# EmgAcq.net
KiCad netlist of a schematic drawn in Altium Designer
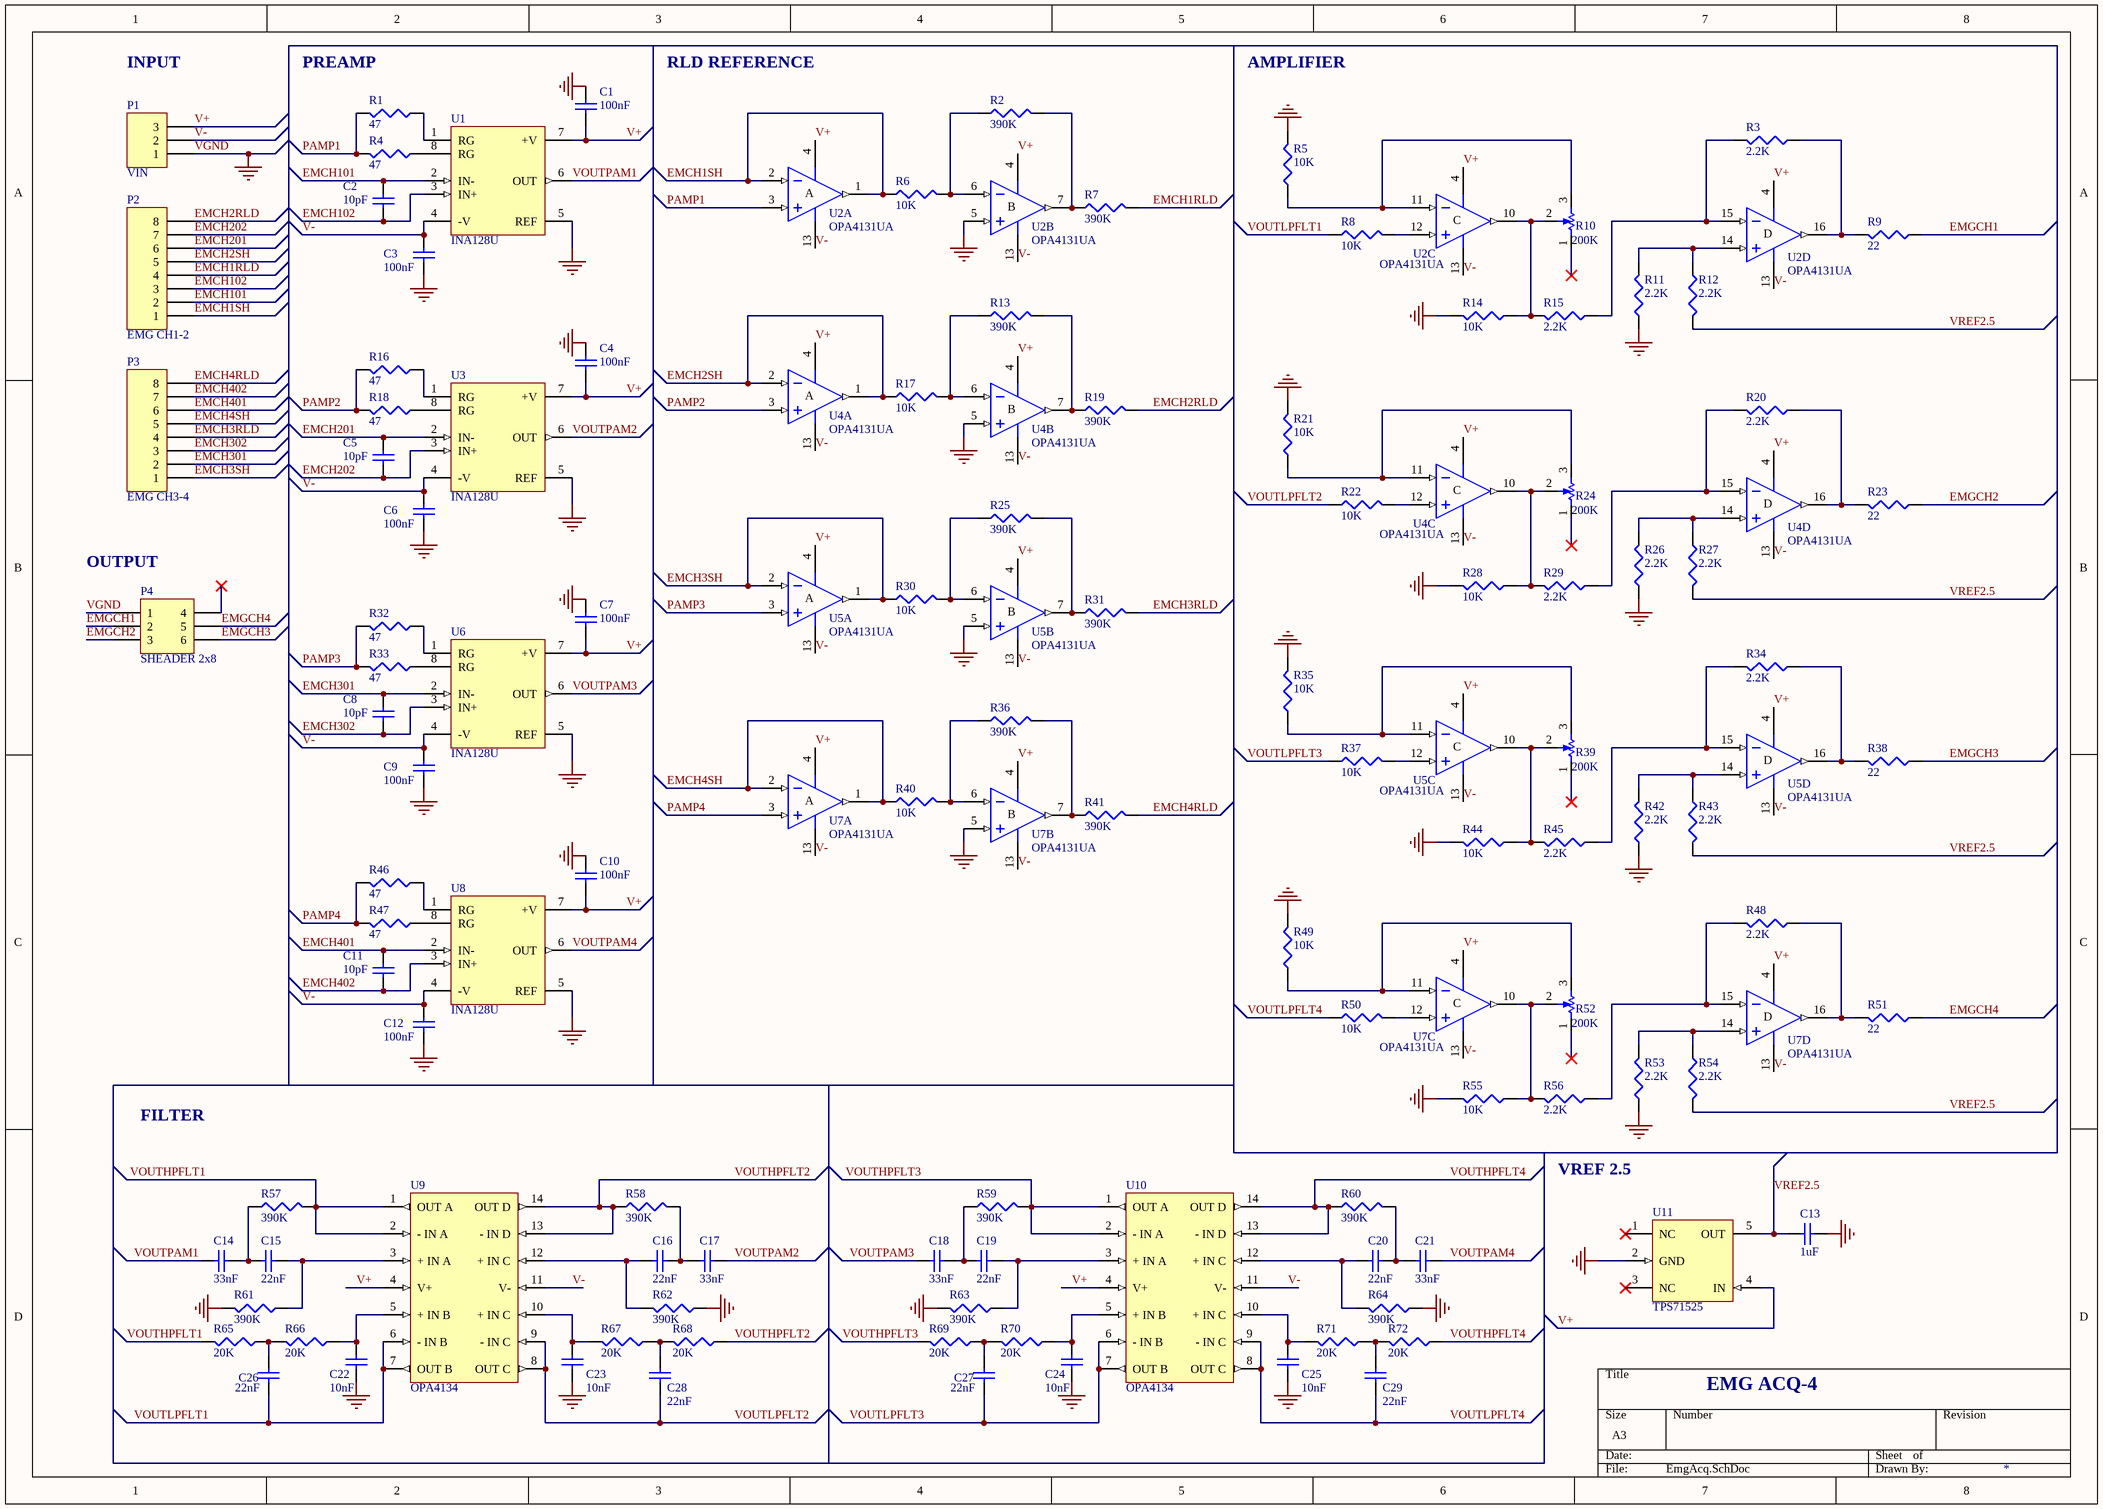
[diagram p0: EmgAcq.SchDoc]

(export (version "E")
  (design (tool "Eeschema 10.0.6"))
  (components
    (comp (ref "C1")
      (value "100nF")
      (footprint "C1206")
      (description "Capacitor (Semiconductor SIM Model)")
      (fields (field (name "Comment") "Cap Semi"))
      (libsource (lib "Miscellaneous Devices") (part "Cap Semi"))
    )
    (comp (ref "C2")
      (value "10pF")
      (footprint "C1206")
      (description "Capacitor (Semiconductor SIM Model)")
      (fields (field (name "Comment") "Cap Semi"))
      (libsource (lib "Miscellaneous Devices") (part "Cap Semi"))
    )
    (comp (ref "C3")
      (value "100nF")
      (footprint "C1206")
      (description "Capacitor (Semiconductor SIM Model)")
      (fields (field (name "Comment") "Cap Semi"))
      (libsource (lib "Miscellaneous Devices") (part "Cap Semi"))
    )
    (comp (ref "C4")
      (value "100nF")
      (footprint "C1206")
      (description "Capacitor (Semiconductor SIM Model)")
      (fields (field (name "Comment") "Cap Semi"))
      (libsource (lib "Miscellaneous Devices") (part "Cap Semi"))
    )
    (comp (ref "C5")
      (value "10pF")
      (footprint "C1206")
      (description "Capacitor (Semiconductor SIM Model)")
      (fields (field (name "Comment") "Cap Semi"))
      (libsource (lib "Miscellaneous Devices") (part "Cap Semi"))
    )
    (comp (ref "C6")
      (value "100nF")
      (footprint "C1206")
      (description "Capacitor (Semiconductor SIM Model)")
      (fields (field (name "Comment") "Cap Semi"))
      (libsource (lib "Miscellaneous Devices") (part "Cap Semi"))
    )
    (comp (ref "C7")
      (value "100nF")
      (footprint "C1206")
      (description "Capacitor (Semiconductor SIM Model)")
      (fields (field (name "Comment") "Cap Semi"))
      (libsource (lib "Miscellaneous Devices") (part "Cap Semi"))
    )
    (comp (ref "C8")
      (value "10pF")
      (footprint "C1206")
      (description "Capacitor (Semiconductor SIM Model)")
      (fields (field (name "Comment") "Cap Semi"))
      (libsource (lib "Miscellaneous Devices") (part "Cap Semi"))
    )
    (comp (ref "C9")
      (value "100nF")
      (footprint "C1206")
      (description "Capacitor (Semiconductor SIM Model)")
      (fields (field (name "Comment") "Cap Semi"))
      (libsource (lib "Miscellaneous Devices") (part "Cap Semi"))
    )
    (comp (ref "C10")
      (value "100nF")
      (footprint "C1206")
      (description "Capacitor (Semiconductor SIM Model)")
      (fields (field (name "Comment") "Cap Semi"))
      (libsource (lib "Miscellaneous Devices") (part "Cap Semi"))
    )
    (comp (ref "C11")
      (value "10pF")
      (footprint "C1206")
      (description "Capacitor (Semiconductor SIM Model)")
      (fields (field (name "Comment") "Cap Semi"))
      (libsource (lib "Miscellaneous Devices") (part "Cap Semi"))
    )
    (comp (ref "C12")
      (value "100nF")
      (footprint "C1206")
      (description "Capacitor (Semiconductor SIM Model)")
      (fields (field (name "Comment") "Cap Semi"))
      (libsource (lib "Miscellaneous Devices") (part "Cap Semi"))
    )
    (comp (ref "C13")
      (value "1uF")
      (footprint "CAPC2012M")
      (description "Capacitor (Semiconductor SIM Model)")
      (fields (field (name "Comment") "Cap Semi"))
      (libsource (lib "Miscellaneous Devices") (part "Cap Semi"))
    )
    (comp (ref "C14")
      (value "33nF")
      (footprint "C1206")
      (description "Capacitor (Semiconductor SIM Model)")
      (fields (field (name "Comment") "Cap Semi"))
      (libsource (lib "Miscellaneous Devices") (part "Cap Semi"))
    )
    (comp (ref "C15")
      (value "22nF")
      (footprint "1608[0603]")
      (description "Capacitor (Semiconductor SIM Model)")
      (fields (field (name "Comment") "Cap Semi"))
      (libsource (lib "Miscellaneous Devices") (part "Cap Semi"))
    )
    (comp (ref "C16")
      (value "22nF")
      (footprint "1608[0603]")
      (description "Capacitor (Semiconductor SIM Model)")
      (fields (field (name "Comment") "Cap Semi"))
      (libsource (lib "Miscellaneous Devices") (part "Cap Semi"))
    )
    (comp (ref "C17")
      (value "33nF")
      (footprint "C1206")
      (description "Capacitor (Semiconductor SIM Model)")
      (fields (field (name "Comment") "Cap Semi"))
      (libsource (lib "Miscellaneous Devices") (part "Cap Semi"))
    )
    (comp (ref "C18")
      (value "33nF")
      (footprint "C1206")
      (description "Capacitor (Semiconductor SIM Model)")
      (fields (field (name "Comment") "Cap Semi"))
      (libsource (lib "Miscellaneous Devices") (part "Cap Semi"))
    )
    (comp (ref "C19")
      (value "22nF")
      (footprint "1608[0603]")
      (description "Capacitor (Semiconductor SIM Model)")
      (fields (field (name "Comment") "Cap Semi"))
      (libsource (lib "Miscellaneous Devices") (part "Cap Semi"))
    )
    (comp (ref "C20")
      (value "22nF")
      (footprint "1608[0603]")
      (description "Capacitor (Semiconductor SIM Model)")
      (fields (field (name "Comment") "Cap Semi"))
      (libsource (lib "Miscellaneous Devices") (part "Cap Semi"))
    )
    (comp (ref "C21")
      (value "33nF")
      (footprint "C1206")
      (description "Capacitor (Semiconductor SIM Model)")
      (fields (field (name "Comment") "Cap Semi"))
      (libsource (lib "Miscellaneous Devices") (part "Cap Semi"))
    )
    (comp (ref "C22")
      (value "10nF")
      (footprint "C1206")
      (description "Capacitor (Semiconductor SIM Model)")
      (fields (field (name "Comment") "Cap Semi"))
      (libsource (lib "Miscellaneous Devices") (part "Cap Semi"))
    )
    (comp (ref "C23")
      (value "10nF")
      (footprint "C1206")
      (description "Capacitor (Semiconductor SIM Model)")
      (fields (field (name "Comment") "Cap Semi"))
      (libsource (lib "Miscellaneous Devices") (part "Cap Semi"))
    )
    (comp (ref "C24")
      (value "10nF")
      (footprint "C1206")
      (description "Capacitor (Semiconductor SIM Model)")
      (fields (field (name "Comment") "Cap Semi"))
      (libsource (lib "Miscellaneous Devices") (part "Cap Semi"))
    )
    (comp (ref "C25")
      (value "10nF")
      (footprint "C1206")
      (description "Capacitor (Semiconductor SIM Model)")
      (fields (field (name "Comment") "Cap Semi"))
      (libsource (lib "Miscellaneous Devices") (part "Cap Semi"))
    )
    (comp (ref "C26")
      (value "22nF")
      (footprint "1608[0603]")
      (description "Capacitor (Semiconductor SIM Model)")
      (fields (field (name "Comment") "Cap Semi"))
      (libsource (lib "Miscellaneous Devices") (part "Cap Semi"))
    )
    (comp (ref "C27")
      (value "22nF")
      (footprint "1608[0603]")
      (description "Capacitor (Semiconductor SIM Model)")
      (fields (field (name "Comment") "Cap Semi"))
      (libsource (lib "Miscellaneous Devices") (part "Cap Semi"))
    )
    (comp (ref "C28")
      (value "22nF")
      (footprint "1608[0603]")
      (description "Capacitor (Semiconductor SIM Model)")
      (fields (field (name "Comment") "Cap Semi"))
      (libsource (lib "Miscellaneous Devices") (part "Cap Semi"))
    )
    (comp (ref "C29")
      (value "22nF")
      (footprint "1608[0603]")
      (description "Capacitor (Semiconductor SIM Model)")
      (fields (field (name "Comment") "Cap Semi"))
      (libsource (lib "Miscellaneous Devices") (part "Cap Semi"))
    )
    (comp (ref "P1")
      (value "VIN")
      (footprint "AZUL5-3")
      (description "Header, 3-Pin")
      (libsource (lib "Miscellaneous Connectors") (part "Header 3"))
    )
    (comp (ref "P2")
      (value "EMG CH1-2")
      (footprint "AZUL5-8")
      (description "Header, 8-Pin")
      (libsource (lib "Miscellaneous Connectors") (part "Header 8"))
    )
    (comp (ref "P3")
      (value "EMG CH3-4")
      (footprint "AZUL5-8")
      (description "Header, 8-Pin")
      (libsource (lib "Miscellaneous Connectors") (part "Header 8"))
    )
    (comp (ref "P4")
      (value "SHEADER 2x8")
      (footprint "SHBH 2x3")
      (description "Shrouded Box Header: 2x8-Pin, 0.100\" (2.54 mm) Male")
      (libsource (lib "LitoLibrary") (part "SB Header 2x3"))
    )
    (comp (ref "R1")
      (value "47")
      (footprint "RESC3225M")
      (description "Resistor")
      (fields (field (name "Comment") "Res3"))
      (libsource (lib "Miscellaneous Devices") (part "Res3"))
    )
    (comp (ref "R2")
      (value "390K")
      (footprint "RESC3225M")
      (description "Resistor")
      (fields (field (name "Comment") "Res3"))
      (libsource (lib "Miscellaneous Devices") (part "Res3"))
    )
    (comp (ref "R3")
      (value "2.2K")
      (footprint "RESC3225M")
      (description "Resistor")
      (fields (field (name "Comment") "Res3"))
      (libsource (lib "Miscellaneous Devices") (part "Res3"))
    )
    (comp (ref "R4")
      (value "47")
      (footprint "RESC3225M")
      (description "Resistor")
      (fields (field (name "Comment") "Res3"))
      (libsource (lib "Miscellaneous Devices") (part "Res3"))
    )
    (comp (ref "R5")
      (value "10K")
      (footprint "RESC3225M")
      (description "Resistor")
      (fields (field (name "Comment") "Res3"))
      (libsource (lib "Miscellaneous Devices") (part "Res3"))
    )
    (comp (ref "R6")
      (value "10K")
      (footprint "RESC3225M")
      (description "Resistor")
      (fields (field (name "Comment") "Res3"))
      (libsource (lib "Miscellaneous Devices") (part "Res3"))
    )
    (comp (ref "R7")
      (value "390K")
      (footprint "RESC3225M")
      (description "Resistor")
      (fields (field (name "Comment") "Res3"))
      (libsource (lib "Miscellaneous Devices") (part "Res3"))
    )
    (comp (ref "R8")
      (value "10K")
      (footprint "RESC3225M")
      (description "Resistor")
      (fields (field (name "Comment") "Res3"))
      (libsource (lib "Miscellaneous Devices") (part "Res3"))
    )
    (comp (ref "R9")
      (value "22")
      (footprint "RESC3225M")
      (description "Resistor")
      (fields (field (name "Comment") "Res3"))
      (libsource (lib "Miscellaneous Devices") (part "Res3"))
    )
    (comp (ref "R10")
      (value "POT3361")
      (footprint "3361P")
      (fields (field (name "ALTIUM_UNNAMED_1") "200K"))
      (libsource (lib "LitoLibrary") (part "POT3361"))
    )
    (comp (ref "R11")
      (value "2.2K")
      (footprint "RESC3225M")
      (description "Resistor")
      (fields (field (name "Comment") "Res3"))
      (libsource (lib "Miscellaneous Devices") (part "Res3"))
    )
    (comp (ref "R12")
      (value "2.2K")
      (footprint "RESC3225M")
      (description "Resistor")
      (fields (field (name "Comment") "Res3"))
      (libsource (lib "Miscellaneous Devices") (part "Res3"))
    )
    (comp (ref "R13")
      (value "390K")
      (footprint "RESC3225M")
      (description "Resistor")
      (fields (field (name "Comment") "Res3"))
      (libsource (lib "Miscellaneous Devices") (part "Res3"))
    )
    (comp (ref "R14")
      (value "10K")
      (footprint "RESC3225M")
      (description "Resistor")
      (fields (field (name "Comment") "Res3"))
      (libsource (lib "Miscellaneous Devices") (part "Res3"))
    )
    (comp (ref "R15")
      (value "2.2K")
      (footprint "RESC3225M")
      (description "Resistor")
      (fields (field (name "Comment") "Res3"))
      (libsource (lib "Miscellaneous Devices") (part "Res3"))
    )
    (comp (ref "R16")
      (value "47")
      (footprint "RESC3225M")
      (description "Resistor")
      (fields (field (name "Comment") "Res3"))
      (libsource (lib "Miscellaneous Devices") (part "Res3"))
    )
    (comp (ref "R17")
      (value "10K")
      (footprint "RESC3225M")
      (description "Resistor")
      (fields (field (name "Comment") "Res3"))
      (libsource (lib "Miscellaneous Devices") (part "Res3"))
    )
    (comp (ref "R18")
      (value "47")
      (footprint "RESC3225M")
      (description "Resistor")
      (fields (field (name "Comment") "Res3"))
      (libsource (lib "Miscellaneous Devices") (part "Res3"))
    )
    (comp (ref "R19")
      (value "390K")
      (footprint "RESC3225M")
      (description "Resistor")
      (fields (field (name "Comment") "Res3"))
      (libsource (lib "Miscellaneous Devices") (part "Res3"))
    )
    (comp (ref "R20")
      (value "2.2K")
      (footprint "RESC3225M")
      (description "Resistor")
      (fields (field (name "Comment") "Res3"))
      (libsource (lib "Miscellaneous Devices") (part "Res3"))
    )
    (comp (ref "R21")
      (value "10K")
      (footprint "RESC3225M")
      (description "Resistor")
      (fields (field (name "Comment") "Res3"))
      (libsource (lib "Miscellaneous Devices") (part "Res3"))
    )
    (comp (ref "R22")
      (value "10K")
      (footprint "RESC3225M")
      (description "Resistor")
      (fields (field (name "Comment") "Res3"))
      (libsource (lib "Miscellaneous Devices") (part "Res3"))
    )
    (comp (ref "R23")
      (value "22")
      (footprint "RESC3225M")
      (description "Resistor")
      (fields (field (name "Comment") "Res3"))
      (libsource (lib "Miscellaneous Devices") (part "Res3"))
    )
    (comp (ref "R24")
      (value "POT3361")
      (footprint "3361P")
      (fields (field (name "ALTIUM_UNNAMED_1") "200K"))
      (libsource (lib "LitoLibrary") (part "POT3361"))
    )
    (comp (ref "R25")
      (value "390K")
      (footprint "RESC3225M")
      (description "Resistor")
      (fields (field (name "Comment") "Res3"))
      (libsource (lib "Miscellaneous Devices") (part "Res3"))
    )
    (comp (ref "R26")
      (value "2.2K")
      (footprint "RESC3225M")
      (description "Resistor")
      (fields (field (name "Comment") "Res3"))
      (libsource (lib "Miscellaneous Devices") (part "Res3"))
    )
    (comp (ref "R27")
      (value "2.2K")
      (footprint "RESC3225M")
      (description "Resistor")
      (fields (field (name "Comment") "Res3"))
      (libsource (lib "Miscellaneous Devices") (part "Res3"))
    )
    (comp (ref "R28")
      (value "10K")
      (footprint "RESC3225M")
      (description "Resistor")
      (fields (field (name "Comment") "Res3"))
      (libsource (lib "Miscellaneous Devices") (part "Res3"))
    )
    (comp (ref "R29")
      (value "2.2K")
      (footprint "RESC3225M")
      (description "Resistor")
      (fields (field (name "Comment") "Res3"))
      (libsource (lib "Miscellaneous Devices") (part "Res3"))
    )
    (comp (ref "R30")
      (value "10K")
      (footprint "RESC3225M")
      (description "Resistor")
      (fields (field (name "Comment") "Res3"))
      (libsource (lib "Miscellaneous Devices") (part "Res3"))
    )
    (comp (ref "R31")
      (value "390K")
      (footprint "RESC3225M")
      (description "Resistor")
      (fields (field (name "Comment") "Res3"))
      (libsource (lib "Miscellaneous Devices") (part "Res3"))
    )
    (comp (ref "R32")
      (value "47")
      (footprint "RESC3225M")
      (description "Resistor")
      (fields (field (name "Comment") "Res3"))
      (libsource (lib "Miscellaneous Devices") (part "Res3"))
    )
    (comp (ref "R33")
      (value "47")
      (footprint "RESC3225M")
      (description "Resistor")
      (fields (field (name "Comment") "Res3"))
      (libsource (lib "Miscellaneous Devices") (part "Res3"))
    )
    (comp (ref "R34")
      (value "2.2K")
      (footprint "RESC3225M")
      (description "Resistor")
      (fields (field (name "Comment") "Res3"))
      (libsource (lib "Miscellaneous Devices") (part "Res3"))
    )
    (comp (ref "R35")
      (value "10K")
      (footprint "RESC3225M")
      (description "Resistor")
      (fields (field (name "Comment") "Res3"))
      (libsource (lib "Miscellaneous Devices") (part "Res3"))
    )
    (comp (ref "R36")
      (value "390K")
      (footprint "RESC3225M")
      (description "Resistor")
      (fields (field (name "Comment") "Res3"))
      (libsource (lib "Miscellaneous Devices") (part "Res3"))
    )
    (comp (ref "R37")
      (value "10K")
      (footprint "RESC3225M")
      (description "Resistor")
      (fields (field (name "Comment") "Res3"))
      (libsource (lib "Miscellaneous Devices") (part "Res3"))
    )
    (comp (ref "R38")
      (value "22")
      (footprint "RESC3225M")
      (description "Resistor")
      (fields (field (name "Comment") "Res3"))
      (libsource (lib "Miscellaneous Devices") (part "Res3"))
    )
    (comp (ref "R39")
      (value "POT3361")
      (footprint "3361P")
      (fields (field (name "ALTIUM_UNNAMED_1") "200K"))
      (libsource (lib "LitoLibrary") (part "POT3361"))
    )
    (comp (ref "R40")
      (value "10K")
      (footprint "RESC3225M")
      (description "Resistor")
      (fields (field (name "Comment") "Res3"))
      (libsource (lib "Miscellaneous Devices") (part "Res3"))
    )
    (comp (ref "R41")
      (value "390K")
      (footprint "RESC3225M")
      (description "Resistor")
      (fields (field (name "Comment") "Res3"))
      (libsource (lib "Miscellaneous Devices") (part "Res3"))
    )
    (comp (ref "R42")
      (value "2.2K")
      (footprint "RESC3225M")
      (description "Resistor")
      (fields (field (name "Comment") "Res3"))
      (libsource (lib "Miscellaneous Devices") (part "Res3"))
    )
    (comp (ref "R43")
      (value "2.2K")
      (footprint "RESC3225M")
      (description "Resistor")
      (fields (field (name "Comment") "Res3"))
      (libsource (lib "Miscellaneous Devices") (part "Res3"))
    )
    (comp (ref "R44")
      (value "10K")
      (footprint "RESC3225M")
      (description "Resistor")
      (fields (field (name "Comment") "Res3"))
      (libsource (lib "Miscellaneous Devices") (part "Res3"))
    )
    (comp (ref "R45")
      (value "2.2K")
      (footprint "RESC3225M")
      (description "Resistor")
      (fields (field (name "Comment") "Res3"))
      (libsource (lib "Miscellaneous Devices") (part "Res3"))
    )
    (comp (ref "R46")
      (value "47")
      (footprint "RESC3225M")
      (description "Resistor")
      (fields (field (name "Comment") "Res3"))
      (libsource (lib "Miscellaneous Devices") (part "Res3"))
    )
    (comp (ref "R47")
      (value "47")
      (footprint "RESC3225M")
      (description "Resistor")
      (fields (field (name "Comment") "Res3"))
      (libsource (lib "Miscellaneous Devices") (part "Res3"))
    )
    (comp (ref "R48")
      (value "2.2K")
      (footprint "RESC3225M")
      (description "Resistor")
      (fields (field (name "Comment") "Res3"))
      (libsource (lib "Miscellaneous Devices") (part "Res3"))
    )
    (comp (ref "R49")
      (value "10K")
      (footprint "RESC3225M")
      (description "Resistor")
      (fields (field (name "Comment") "Res3"))
      (libsource (lib "Miscellaneous Devices") (part "Res3"))
    )
    (comp (ref "R50")
      (value "10K")
      (footprint "RESC3225M")
      (description "Resistor")
      (fields (field (name "Comment") "Res3"))
      (libsource (lib "Miscellaneous Devices") (part "Res3"))
    )
    (comp (ref "R51")
      (value "22")
      (footprint "RESC3225M")
      (description "Resistor")
      (fields (field (name "Comment") "Res3"))
      (libsource (lib "Miscellaneous Devices") (part "Res3"))
    )
    (comp (ref "R52")
      (value "POT3361")
      (footprint "3361P")
      (fields (field (name "ALTIUM_UNNAMED_1") "200K"))
      (libsource (lib "LitoLibrary") (part "POT3361"))
    )
    (comp (ref "R53")
      (value "2.2K")
      (footprint "RESC3225M")
      (description "Resistor")
      (fields (field (name "Comment") "Res3"))
      (libsource (lib "Miscellaneous Devices") (part "Res3"))
    )
    (comp (ref "R54")
      (value "2.2K")
      (footprint "RESC3225M")
      (description "Resistor")
      (fields (field (name "Comment") "Res3"))
      (libsource (lib "Miscellaneous Devices") (part "Res3"))
    )
    (comp (ref "R55")
      (value "10K")
      (footprint "RESC3225M")
      (description "Resistor")
      (fields (field (name "Comment") "Res3"))
      (libsource (lib "Miscellaneous Devices") (part "Res3"))
    )
    (comp (ref "R56")
      (value "2.2K")
      (footprint "RESC3225M")
      (description "Resistor")
      (fields (field (name "Comment") "Res3"))
      (libsource (lib "Miscellaneous Devices") (part "Res3"))
    )
    (comp (ref "R57")
      (value "390K")
      (footprint "RESC3225M")
      (description "Resistor")
      (fields (field (name "Comment") "Res3"))
      (libsource (lib "Miscellaneous Devices") (part "Res3"))
    )
    (comp (ref "R58")
      (value "390K")
      (footprint "RESC3225M")
      (description "Resistor")
      (fields (field (name "Comment") "Res3"))
      (libsource (lib "Miscellaneous Devices") (part "Res3"))
    )
    (comp (ref "R59")
      (value "390K")
      (footprint "RESC3225M")
      (description "Resistor")
      (fields (field (name "Comment") "Res3"))
      (libsource (lib "Miscellaneous Devices") (part "Res3"))
    )
    (comp (ref "R60")
      (value "390K")
      (footprint "RESC3225M")
      (description "Resistor")
      (fields (field (name "Comment") "Res3"))
      (libsource (lib "Miscellaneous Devices") (part "Res3"))
    )
    (comp (ref "R61")
      (value "390K")
      (footprint "RESC3225M")
      (description "Resistor")
      (fields (field (name "Comment") "Res3"))
      (libsource (lib "Miscellaneous Devices") (part "Res3"))
    )
    (comp (ref "R62")
      (value "390K")
      (footprint "RESC3225M")
      (description "Resistor")
      (fields (field (name "Comment") "Res3"))
      (libsource (lib "Miscellaneous Devices") (part "Res3"))
    )
    (comp (ref "R63")
      (value "390K")
      (footprint "RESC3225M")
      (description "Resistor")
      (fields (field (name "Comment") "Res3"))
      (libsource (lib "Miscellaneous Devices") (part "Res3"))
    )
    (comp (ref "R64")
      (value "390K")
      (footprint "RESC3225M")
      (description "Resistor")
      (fields (field (name "Comment") "Res3"))
      (libsource (lib "Miscellaneous Devices") (part "Res3"))
    )
    (comp (ref "R65")
      (value "20K")
      (footprint "RESC3225M")
      (description "Resistor")
      (fields (field (name "Comment") "Res3"))
      (libsource (lib "Miscellaneous Devices") (part "Res3"))
    )
    (comp (ref "R66")
      (value "20K")
      (footprint "RESC3225M")
      (description "Resistor")
      (fields (field (name "Comment") "Res3"))
      (libsource (lib "Miscellaneous Devices") (part "Res3"))
    )
    (comp (ref "R67")
      (value "20K")
      (footprint "RESC3225M")
      (description "Resistor")
      (fields (field (name "Comment") "Res3"))
      (libsource (lib "Miscellaneous Devices") (part "Res3"))
    )
    (comp (ref "R68")
      (value "20K")
      (footprint "RESC3225M")
      (description "Resistor")
      (fields (field (name "Comment") "Res3"))
      (libsource (lib "Miscellaneous Devices") (part "Res3"))
    )
    (comp (ref "R69")
      (value "20K")
      (footprint "RESC3225M")
      (description "Resistor")
      (fields (field (name "Comment") "Res3"))
      (libsource (lib "Miscellaneous Devices") (part "Res3"))
    )
    (comp (ref "R70")
      (value "20K")
      (footprint "RESC3225M")
      (description "Resistor")
      (fields (field (name "Comment") "Res3"))
      (libsource (lib "Miscellaneous Devices") (part "Res3"))
    )
    (comp (ref "R71")
      (value "20K")
      (footprint "RESC3225M")
      (description "Resistor")
      (fields (field (name "Comment") "Res3"))
      (libsource (lib "Miscellaneous Devices") (part "Res3"))
    )
    (comp (ref "R72")
      (value "20K")
      (footprint "RESC3225M")
      (description "Resistor")
      (fields (field (name "Comment") "Res3"))
      (libsource (lib "Miscellaneous Devices") (part "Res3"))
    )
    (comp (ref "U1")
      (value "INA128U")
      (footprint "182H_N")
      (description "Precision, Low-Power Instrumentation Amplifiers")
      (libsource (lib "BB Instrumentation Amplifier") (part "INA128U"))
    )
    (comp (ref "U2")
      (value "OPA4131UA")
      (footprint "211F_N")
      (description "General Purpose FET-Input Operational Amplifiers")
      (libsource (lib "BB Operational Amplifier") (part "OPA4131UA"))
    )
    (comp (ref "U3")
      (value "INA128U")
      (footprint "182H_N")
      (description "Precision, Low-Power Instrumentation Amplifiers")
      (libsource (lib "BB Instrumentation Amplifier") (part "INA128U"))
    )
    (comp (ref "U4")
      (value "OPA4131UA")
      (footprint "211F_N")
      (description "General Purpose FET-Input Operational Amplifiers")
      (libsource (lib "BB Operational Amplifier") (part "OPA4131UA"))
    )
    (comp (ref "U5")
      (value "OPA4131UA")
      (footprint "211F_N")
      (description "General Purpose FET-Input Operational Amplifiers")
      (libsource (lib "BB Operational Amplifier") (part "OPA4131UA"))
    )
    (comp (ref "U6")
      (value "INA128U")
      (footprint "182H_N")
      (description "Precision, Low-Power Instrumentation Amplifiers")
      (libsource (lib "BB Instrumentation Amplifier") (part "INA128U"))
    )
    (comp (ref "U7")
      (value "OPA4131UA")
      (footprint "211F_N")
      (description "General Purpose FET-Input Operational Amplifiers")
      (libsource (lib "BB Operational Amplifier") (part "OPA4131UA"))
    )
    (comp (ref "U8")
      (value "INA128U")
      (footprint "182H_N")
      (description "Precision, Low-Power Instrumentation Amplifiers")
      (libsource (lib "BB Instrumentation Amplifier") (part "INA128U"))
    )
    (comp (ref "U9")
      (value "OPA4134")
      (footprint "SOIC127P600-14M")
      (libsource (lib "LitoLibrary") (part "OPA4134"))
    )
    (comp (ref "U10")
      (value "OPA4134")
      (footprint "SOIC127P600-14M")
      (libsource (lib "LitoLibrary") (part "OPA4134"))
    )
    (comp (ref "U11")
      (value "TPS71525")
      (footprint "SOT353-5L")
      (libsource (lib "LitoLibrary") (part "TPS71525"))
    )
  )
  (nets
    (net (code "1") (name "/EMCH1RLD") (class "Default")
      (node (ref "P2") (pin "4") (pinfunction "4_4") (pintype "passive"))
      (node (ref "R7") (pin "2") (pinfunction "2_2") (pintype "passive"))
    )
    (net (code "2") (name "/EMCH1SH") (class "Default")
      (node (ref "P2") (pin "1") (pinfunction "1_1") (pintype "passive"))
      (node (ref "R6") (pin "1") (pinfunction "1_1") (pintype "passive"))
      (node (ref "U2") (pin "1") (pinfunction "OUT_1") (pintype "output"))
      (node (ref "U2") (pin "2") (pinfunction "IN-_2") (pintype "input"))
    )
    (net (code "3") (name "/EMCH2RLD") (class "Default")
      (node (ref "P2") (pin "8") (pinfunction "8_8") (pintype "passive"))
      (node (ref "R19") (pin "2") (pinfunction "2_2") (pintype "passive"))
    )
    (net (code "4") (name "/EMCH2SH") (class "Default")
      (node (ref "P2") (pin "5") (pinfunction "5_5") (pintype "passive"))
      (node (ref "R17") (pin "1") (pinfunction "1_1") (pintype "passive"))
      (node (ref "U4") (pin "1") (pinfunction "OUT_1") (pintype "output"))
      (node (ref "U4") (pin "2") (pinfunction "IN-_2") (pintype "input"))
    )
    (net (code "5") (name "/EMCH3RLD") (class "Default")
      (node (ref "P3") (pin "4") (pinfunction "4_4") (pintype "passive"))
      (node (ref "R31") (pin "2") (pinfunction "2_2") (pintype "passive"))
    )
    (net (code "6") (name "/EMCH3SH") (class "Default")
      (node (ref "P3") (pin "1") (pinfunction "1_1") (pintype "passive"))
      (node (ref "R30") (pin "1") (pinfunction "1_1") (pintype "passive"))
      (node (ref "U5") (pin "1") (pinfunction "OUT_1") (pintype "output"))
      (node (ref "U5") (pin "2") (pinfunction "IN-_2") (pintype "input"))
    )
    (net (code "7") (name "/EMCH4RLD") (class "Default")
      (node (ref "P3") (pin "8") (pinfunction "8_8") (pintype "passive"))
      (node (ref "R41") (pin "2") (pinfunction "2_2") (pintype "passive"))
    )
    (net (code "8") (name "/EMCH4SH") (class "Default")
      (node (ref "P3") (pin "5") (pinfunction "5_5") (pintype "passive"))
      (node (ref "R40") (pin "1") (pinfunction "1_1") (pintype "passive"))
      (node (ref "U7") (pin "1") (pinfunction "OUT_1") (pintype "output"))
      (node (ref "U7") (pin "2") (pinfunction "IN-_2") (pintype "input"))
    )
    (net (code "9") (name "/EMCH101") (class "Default")
      (node (ref "C2") (pin "2") (pinfunction "2_2") (pintype "passive"))
      (node (ref "P2") (pin "2") (pinfunction "2_2") (pintype "passive"))
      (node (ref "U1") (pin "2") (pinfunction "IN-_2") (pintype "input"))
    )
    (net (code "10") (name "/EMCH102") (class "Default")
      (node (ref "C2") (pin "1") (pinfunction "1_1") (pintype "passive"))
      (node (ref "P2") (pin "3") (pinfunction "3_3") (pintype "passive"))
      (node (ref "U1") (pin "3") (pinfunction "IN+_3") (pintype "input"))
    )
    (net (code "11") (name "/EMCH201") (class "Default")
      (node (ref "C5") (pin "2") (pinfunction "2_2") (pintype "passive"))
      (node (ref "P2") (pin "6") (pinfunction "6_6") (pintype "passive"))
      (node (ref "U3") (pin "2") (pinfunction "IN-_2") (pintype "input"))
    )
    (net (code "12") (name "/EMCH202") (class "Default")
      (node (ref "C5") (pin "1") (pinfunction "1_1") (pintype "passive"))
      (node (ref "P2") (pin "7") (pinfunction "7_7") (pintype "passive"))
      (node (ref "U3") (pin "3") (pinfunction "IN+_3") (pintype "input"))
    )
    (net (code "13") (name "/EMCH301") (class "Default")
      (node (ref "C8") (pin "2") (pinfunction "2_2") (pintype "passive"))
      (node (ref "P3") (pin "2") (pinfunction "2_2") (pintype "passive"))
      (node (ref "U6") (pin "2") (pinfunction "IN-_2") (pintype "input"))
    )
    (net (code "14") (name "/EMCH302") (class "Default")
      (node (ref "C8") (pin "1") (pinfunction "1_1") (pintype "passive"))
      (node (ref "P3") (pin "3") (pinfunction "3_3") (pintype "passive"))
      (node (ref "U6") (pin "3") (pinfunction "IN+_3") (pintype "input"))
    )
    (net (code "15") (name "/EMCH401") (class "Default")
      (node (ref "C11") (pin "2") (pinfunction "2_2") (pintype "passive"))
      (node (ref "P3") (pin "6") (pinfunction "6_6") (pintype "passive"))
      (node (ref "U8") (pin "2") (pinfunction "IN-_2") (pintype "input"))
    )
    (net (code "16") (name "/EMCH402") (class "Default")
      (node (ref "C11") (pin "1") (pinfunction "1_1") (pintype "passive"))
      (node (ref "P3") (pin "7") (pinfunction "7_7") (pintype "passive"))
      (node (ref "U8") (pin "3") (pinfunction "IN+_3") (pintype "input"))
    )
    (net (code "17") (name "/EMGCH1") (class "Default")
      (node (ref "P4") (pin "2") (pinfunction "2_2") (pintype "passive"))
      (node (ref "R9") (pin "2") (pinfunction "2_2") (pintype "passive"))
    )
    (net (code "18") (name "/EMGCH2") (class "Default")
      (node (ref "P4") (pin "3") (pinfunction "3_3") (pintype "passive"))
      (node (ref "R23") (pin "2") (pinfunction "2_2") (pintype "passive"))
    )
    (net (code "19") (name "/EMGCH3") (class "Default")
      (node (ref "P4") (pin "6") (pinfunction "6_6") (pintype "passive"))
      (node (ref "R38") (pin "2") (pinfunction "2_2") (pintype "passive"))
    )
    (net (code "20") (name "/EMGCH4") (class "Default")
      (node (ref "P4") (pin "5") (pinfunction "5_5") (pintype "passive"))
      (node (ref "R51") (pin "2") (pinfunction "2_2") (pintype "passive"))
    )
    (net (code "21") (name "/PAMP1") (class "Default")
      (node (ref "R1") (pin "2") (pinfunction "2_2") (pintype "passive"))
      (node (ref "R4") (pin "2") (pinfunction "2_2") (pintype "passive"))
      (node (ref "U2") (pin "3") (pinfunction "IN+_3") (pintype "input"))
    )
    (net (code "22") (name "/PAMP2") (class "Default")
      (node (ref "R16") (pin "2") (pinfunction "2_2") (pintype "passive"))
      (node (ref "R18") (pin "2") (pinfunction "2_2") (pintype "passive"))
      (node (ref "U4") (pin "3") (pinfunction "IN+_3") (pintype "input"))
    )
    (net (code "23") (name "/PAMP3") (class "Default")
      (node (ref "R32") (pin "2") (pinfunction "2_2") (pintype "passive"))
      (node (ref "R33") (pin "2") (pinfunction "2_2") (pintype "passive"))
      (node (ref "U5") (pin "3") (pinfunction "IN+_3") (pintype "input"))
    )
    (net (code "24") (name "/PAMP4") (class "Default")
      (node (ref "R46") (pin "2") (pinfunction "2_2") (pintype "passive"))
      (node (ref "R47") (pin "2") (pinfunction "2_2") (pintype "passive"))
      (node (ref "U7") (pin "3") (pinfunction "IN+_3") (pintype "input"))
    )
    (net (code "25") (name "/V+") (class "Default")
      (node (ref "C1") (pin "1") (pinfunction "1_1") (pintype "passive"))
      (node (ref "C10") (pin "1") (pinfunction "1_1") (pintype "passive"))
      (node (ref "C4") (pin "1") (pinfunction "1_1") (pintype "passive"))
      (node (ref "C7") (pin "1") (pinfunction "1_1") (pintype "passive"))
      (node (ref "P1") (pin "3") (pinfunction "3_3") (pintype "passive"))
      (node (ref "U1") (pin "7") (pinfunction "+V_7") (pintype "power_in"))
      (node (ref "U10") (pin "4") (pinfunction "V+_4") (pintype "input"))
      (node (ref "U11") (pin "4") (pinfunction "IN_4") (pintype "input"))
      (node (ref "U2") (pin "4") (pinfunction "V+_4") (pintype "power_in"))
      (node (ref "U3") (pin "7") (pinfunction "+V_7") (pintype "power_in"))
      (node (ref "U4") (pin "4") (pinfunction "V+_4") (pintype "power_in"))
      (node (ref "U5") (pin "4") (pinfunction "V+_4") (pintype "power_in"))
      (node (ref "U6") (pin "7") (pinfunction "+V_7") (pintype "power_in"))
      (node (ref "U7") (pin "4") (pinfunction "V+_4") (pintype "power_in"))
      (node (ref "U8") (pin "7") (pinfunction "+V_7") (pintype "power_in"))
      (node (ref "U9") (pin "4") (pinfunction "V+_4") (pintype "input"))
    )
    (net (code "26") (name "/V-") (class "Default")
      (node (ref "C12") (pin "2") (pinfunction "2_2") (pintype "passive"))
      (node (ref "C3") (pin "2") (pinfunction "2_2") (pintype "passive"))
      (node (ref "C6") (pin "2") (pinfunction "2_2") (pintype "passive"))
      (node (ref "C9") (pin "2") (pinfunction "2_2") (pintype "passive"))
      (node (ref "P1") (pin "2") (pinfunction "2_2") (pintype "passive"))
      (node (ref "U1") (pin "4") (pinfunction "-V_4") (pintype "power_in"))
      (node (ref "U10") (pin "11") (pinfunction "V-_11") (pintype "input"))
      (node (ref "U2") (pin "13") (pinfunction "V-_13") (pintype "power_in"))
      (node (ref "U3") (pin "4") (pinfunction "-V_4") (pintype "power_in"))
      (node (ref "U4") (pin "13") (pinfunction "V-_13") (pintype "power_in"))
      (node (ref "U5") (pin "13") (pinfunction "V-_13") (pintype "power_in"))
      (node (ref "U6") (pin "4") (pinfunction "-V_4") (pintype "power_in"))
      (node (ref "U7") (pin "13") (pinfunction "V-_13") (pintype "power_in"))
      (node (ref "U8") (pin "4") (pinfunction "-V_4") (pintype "power_in"))
      (node (ref "U9") (pin "11") (pinfunction "V-_11") (pintype "input"))
    )
    (net (code "27") (name "/VOUTHPFLT1") (class "Default")
      (node (ref "R57") (pin "2") (pinfunction "2_2") (pintype "passive"))
      (node (ref "R65") (pin "2") (pinfunction "2_2") (pintype "passive"))
      (node (ref "U9") (pin "1") (pinfunction "OUT_A_1") (pintype "output"))
      (node (ref "U9") (pin "2") (pinfunction "-_IN_A_2") (pintype "input"))
    )
    (net (code "28") (name "/VOUTHPFLT2") (class "Default")
      (node (ref "R58") (pin "2") (pinfunction "2_2") (pintype "passive"))
      (node (ref "R68") (pin "2") (pinfunction "2_2") (pintype "passive"))
      (node (ref "U9") (pin "13") (pinfunction "-_IN_D_13") (pintype "input"))
      (node (ref "U9") (pin "14") (pinfunction "OUT_D_14") (pintype "output"))
    )
    (net (code "29") (name "/VOUTHPFLT3") (class "Default")
      (node (ref "R59") (pin "2") (pinfunction "2_2") (pintype "passive"))
      (node (ref "R69") (pin "2") (pinfunction "2_2") (pintype "passive"))
      (node (ref "U10") (pin "1") (pinfunction "OUT_A_1") (pintype "output"))
      (node (ref "U10") (pin "2") (pinfunction "-_IN_A_2") (pintype "input"))
    )
    (net (code "30") (name "/VOUTHPFLT4") (class "Default")
      (node (ref "R60") (pin "2") (pinfunction "2_2") (pintype "passive"))
      (node (ref "R72") (pin "2") (pinfunction "2_2") (pintype "passive"))
      (node (ref "U10") (pin "13") (pinfunction "-_IN_D_13") (pintype "input"))
      (node (ref "U10") (pin "14") (pinfunction "OUT_D_14") (pintype "output"))
    )
    (net (code "31") (name "/VOUTLPFLT1") (class "Default")
      (node (ref "C26") (pin "1") (pinfunction "1_1") (pintype "passive"))
      (node (ref "R8") (pin "2") (pinfunction "2_2") (pintype "passive"))
      (node (ref "U9") (pin "6") (pinfunction "-_IN_B_6") (pintype "input"))
      (node (ref "U9") (pin "7") (pinfunction "OUT_B_7") (pintype "output"))
    )
    (net (code "32") (name "/VOUTLPFLT2") (class "Default")
      (node (ref "C28") (pin "1") (pinfunction "1_1") (pintype "passive"))
      (node (ref "R22") (pin "2") (pinfunction "2_2") (pintype "passive"))
      (node (ref "U9") (pin "8") (pinfunction "OUT_C_8") (pintype "output"))
      (node (ref "U9") (pin "9") (pinfunction "-_IN_C_9") (pintype "input"))
    )
    (net (code "33") (name "/VOUTLPFLT3") (class "Default")
      (node (ref "C27") (pin "1") (pinfunction "1_1") (pintype "passive"))
      (node (ref "R37") (pin "2") (pinfunction "2_2") (pintype "passive"))
      (node (ref "U10") (pin "6") (pinfunction "-_IN_B_6") (pintype "input"))
      (node (ref "U10") (pin "7") (pinfunction "OUT_B_7") (pintype "output"))
    )
    (net (code "34") (name "/VOUTLPFLT4") (class "Default")
      (node (ref "C29") (pin "1") (pinfunction "1_1") (pintype "passive"))
      (node (ref "R50") (pin "2") (pinfunction "2_2") (pintype "passive"))
      (node (ref "U10") (pin "8") (pinfunction "OUT_C_8") (pintype "output"))
      (node (ref "U10") (pin "9") (pinfunction "-_IN_C_9") (pintype "input"))
    )
    (net (code "35") (name "/VOUTPAM1") (class "Default")
      (node (ref "C14") (pin "2") (pinfunction "2_2") (pintype "passive"))
      (node (ref "U1") (pin "6") (pinfunction "OUT_6") (pintype "output"))
    )
    (net (code "36") (name "/VOUTPAM2") (class "Default")
      (node (ref "C17") (pin "2") (pinfunction "2_2") (pintype "passive"))
      (node (ref "U3") (pin "6") (pinfunction "OUT_6") (pintype "output"))
    )
    (net (code "37") (name "/VOUTPAM3") (class "Default")
      (node (ref "C18") (pin "2") (pinfunction "2_2") (pintype "passive"))
      (node (ref "U6") (pin "6") (pinfunction "OUT_6") (pintype "output"))
    )
    (net (code "38") (name "/VOUTPAM4") (class "Default")
      (node (ref "C21") (pin "2") (pinfunction "2_2") (pintype "passive"))
      (node (ref "U8") (pin "6") (pinfunction "OUT_6") (pintype "output"))
    )
    (net (code "39") (name "/VREF2.5") (class "Default")
      (node (ref "C13") (pin "1") (pinfunction "1_1") (pintype "passive"))
      (node (ref "R12") (pin "1") (pinfunction "1_1") (pintype "passive"))
      (node (ref "R27") (pin "1") (pinfunction "1_1") (pintype "passive"))
      (node (ref "R43") (pin "1") (pinfunction "1_1") (pintype "passive"))
      (node (ref "R54") (pin "1") (pinfunction "1_1") (pintype "passive"))
      (node (ref "U11") (pin "5") (pinfunction "OUT_5") (pintype "passive"))
    )
    (net (code "40") (name "GND") (class "Default")
      (node (ref "C1") (pin "2") (pinfunction "2_2") (pintype "passive"))
      (node (ref "C10") (pin "2") (pinfunction "2_2") (pintype "passive"))
      (node (ref "C12") (pin "1") (pinfunction "1_1") (pintype "passive"))
      (node (ref "C13") (pin "2") (pinfunction "2_2") (pintype "passive"))
      (node (ref "C22") (pin "1") (pinfunction "1_1") (pintype "passive"))
      (node (ref "C23") (pin "1") (pinfunction "1_1") (pintype "passive"))
      (node (ref "C24") (pin "1") (pinfunction "1_1") (pintype "passive"))
      (node (ref "C25") (pin "1") (pinfunction "1_1") (pintype "passive"))
      (node (ref "C3") (pin "1") (pinfunction "1_1") (pintype "passive"))
      (node (ref "C4") (pin "2") (pinfunction "2_2") (pintype "passive"))
      (node (ref "C6") (pin "1") (pinfunction "1_1") (pintype "passive"))
      (node (ref "C7") (pin "2") (pinfunction "2_2") (pintype "passive"))
      (node (ref "C9") (pin "1") (pinfunction "1_1") (pintype "passive"))
      (node (ref "P1") (pin "1") (pinfunction "1_1") (pintype "passive"))
      (node (ref "P4") (pin "1") (pinfunction "1_1") (pintype "passive"))
      (node (ref "R11") (pin "2") (pinfunction "2_2") (pintype "passive"))
      (node (ref "R14") (pin "1") (pinfunction "1_1") (pintype "passive"))
      (node (ref "R21") (pin "1") (pinfunction "1_1") (pintype "passive"))
      (node (ref "R26") (pin "2") (pinfunction "2_2") (pintype "passive"))
      (node (ref "R28") (pin "1") (pinfunction "1_1") (pintype "passive"))
      (node (ref "R35") (pin "1") (pinfunction "1_1") (pintype "passive"))
      (node (ref "R42") (pin "2") (pinfunction "2_2") (pintype "passive"))
      (node (ref "R44") (pin "1") (pinfunction "1_1") (pintype "passive"))
      (node (ref "R49") (pin "1") (pinfunction "1_1") (pintype "passive"))
      (node (ref "R5") (pin "1") (pinfunction "1_1") (pintype "passive"))
      (node (ref "R53") (pin "2") (pinfunction "2_2") (pintype "passive"))
      (node (ref "R55") (pin "1") (pinfunction "1_1") (pintype "passive"))
      (node (ref "R61") (pin "2") (pinfunction "2_2") (pintype "passive"))
      (node (ref "R62") (pin "2") (pinfunction "2_2") (pintype "passive"))
      (node (ref "R63") (pin "2") (pinfunction "2_2") (pintype "passive"))
      (node (ref "R64") (pin "2") (pinfunction "2_2") (pintype "passive"))
      (node (ref "U1") (pin "5") (pinfunction "REF_5") (pintype "passive"))
      (node (ref "U11") (pin "2") (pinfunction "GND_2") (pintype "input"))
      (node (ref "U2") (pin "5") (pinfunction "IN+_5") (pintype "input"))
      (node (ref "U3") (pin "5") (pinfunction "REF_5") (pintype "passive"))
      (node (ref "U4") (pin "5") (pinfunction "IN+_5") (pintype "input"))
      (node (ref "U5") (pin "5") (pinfunction "IN+_5") (pintype "input"))
      (node (ref "U6") (pin "5") (pinfunction "REF_5") (pintype "passive"))
      (node (ref "U7") (pin "5") (pinfunction "IN+_5") (pintype "input"))
      (node (ref "U8") (pin "5") (pinfunction "REF_5") (pintype "passive"))
    )
    (net (code "41") (name "Net-(C14-Pad1)") (class "Default")
      (node (ref "C14") (pin "1") (pinfunction "1_1") (pintype "passive"))
      (node (ref "C15") (pin "2") (pinfunction "2_2") (pintype "passive"))
      (node (ref "R57") (pin "1") (pinfunction "1_1") (pintype "passive"))
    )
    (net (code "42") (name "Net-(C16-Pad1)") (class "Default")
      (node (ref "C16") (pin "1") (pinfunction "1_1") (pintype "passive"))
      (node (ref "R62") (pin "1") (pinfunction "1_1") (pintype "passive"))
      (node (ref "U9") (pin "12") (pinfunction "+_IN_C_12") (pintype "input"))
    )
    (net (code "43") (name "Net-(C16-Pad2)") (class "Default")
      (node (ref "C16") (pin "2") (pinfunction "2_2") (pintype "passive"))
      (node (ref "C17") (pin "1") (pinfunction "1_1") (pintype "passive"))
      (node (ref "R58") (pin "1") (pinfunction "1_1") (pintype "passive"))
    )
    (net (code "44") (name "Net-(C18-Pad1)") (class "Default")
      (node (ref "C18") (pin "1") (pinfunction "1_1") (pintype "passive"))
      (node (ref "C19") (pin "2") (pinfunction "2_2") (pintype "passive"))
      (node (ref "R59") (pin "1") (pinfunction "1_1") (pintype "passive"))
    )
    (net (code "45") (name "Net-(C20-Pad1)") (class "Default")
      (node (ref "C20") (pin "1") (pinfunction "1_1") (pintype "passive"))
      (node (ref "R64") (pin "1") (pinfunction "1_1") (pintype "passive"))
      (node (ref "U10") (pin "12") (pinfunction "+_IN_C_12") (pintype "input"))
    )
    (net (code "46") (name "Net-(C20-Pad2)") (class "Default")
      (node (ref "C20") (pin "2") (pinfunction "2_2") (pintype "passive"))
      (node (ref "C21") (pin "1") (pinfunction "1_1") (pintype "passive"))
      (node (ref "R60") (pin "1") (pinfunction "1_1") (pintype "passive"))
    )
    (net (code "47") (name "Net-(C23-Pad2)") (class "Default")
      (node (ref "C23") (pin "2") (pinfunction "2_2") (pintype "passive"))
      (node (ref "R67") (pin "1") (pinfunction "1_1") (pintype "passive"))
      (node (ref "U9") (pin "10") (pinfunction "+_IN_C_10") (pintype "input"))
    )
    (net (code "48") (name "Net-(C25-Pad2)") (class "Default")
      (node (ref "C25") (pin "2") (pinfunction "2_2") (pintype "passive"))
      (node (ref "R71") (pin "1") (pinfunction "1_1") (pintype "passive"))
      (node (ref "U10") (pin "10") (pinfunction "+_IN_C_10") (pintype "input"))
    )
    (net (code "49") (name "Net-(C26-Pad2)") (class "Default")
      (node (ref "C26") (pin "2") (pinfunction "2_2") (pintype "passive"))
      (node (ref "R65") (pin "1") (pinfunction "1_1") (pintype "passive"))
      (node (ref "R66") (pin "2") (pinfunction "2_2") (pintype "passive"))
    )
    (net (code "50") (name "Net-(C27-Pad2)") (class "Default")
      (node (ref "C27") (pin "2") (pinfunction "2_2") (pintype "passive"))
      (node (ref "R69") (pin "1") (pinfunction "1_1") (pintype "passive"))
      (node (ref "R70") (pin "2") (pinfunction "2_2") (pintype "passive"))
    )
    (net (code "51") (name "Net-(C28-Pad2)") (class "Default")
      (node (ref "C28") (pin "2") (pinfunction "2_2") (pintype "passive"))
      (node (ref "R67") (pin "2") (pinfunction "2_2") (pintype "passive"))
      (node (ref "R68") (pin "1") (pinfunction "1_1") (pintype "passive"))
    )
    (net (code "52") (name "Net-(C29-Pad2)") (class "Default")
      (node (ref "C29") (pin "2") (pinfunction "2_2") (pintype "passive"))
      (node (ref "R71") (pin "2") (pinfunction "2_2") (pintype "passive"))
      (node (ref "R72") (pin "1") (pinfunction "1_1") (pintype "passive"))
    )
    (net (code "53") (name "Net-(R1-Pad1)") (class "Default")
      (node (ref "R1") (pin "1") (pinfunction "1_1") (pintype "passive"))
      (node (ref "U1") (pin "1") (pinfunction "RG_1") (pintype "passive"))
    )
    (net (code "54") (name "Net-(R4-Pad1)") (class "Default")
      (node (ref "R4") (pin "1") (pinfunction "1_1") (pintype "passive"))
      (node (ref "U1") (pin "8") (pinfunction "RG_8") (pintype "passive"))
    )
    (net (code "55") (name "Net-(R16-Pad1)") (class "Default")
      (node (ref "R16") (pin "1") (pinfunction "1_1") (pintype "passive"))
      (node (ref "U3") (pin "1") (pinfunction "RG_1") (pintype "passive"))
    )
    (net (code "56") (name "Net-(R18-Pad1)") (class "Default")
      (node (ref "R18") (pin "1") (pinfunction "1_1") (pintype "passive"))
      (node (ref "U3") (pin "8") (pinfunction "RG_8") (pintype "passive"))
    )
    (net (code "57") (name "Net-(R32-Pad1)") (class "Default")
      (node (ref "R32") (pin "1") (pinfunction "1_1") (pintype "passive"))
      (node (ref "U6") (pin "1") (pinfunction "RG_1") (pintype "passive"))
    )
    (net (code "58") (name "Net-(R33-Pad1)") (class "Default")
      (node (ref "R33") (pin "1") (pinfunction "1_1") (pintype "passive"))
      (node (ref "U6") (pin "8") (pinfunction "RG_8") (pintype "passive"))
    )
    (net (code "59") (name "Net-(R46-Pad1)") (class "Default")
      (node (ref "R46") (pin "1") (pinfunction "1_1") (pintype "passive"))
      (node (ref "U8") (pin "1") (pinfunction "RG_1") (pintype "passive"))
    )
    (net (code "60") (name "Net-(R47-Pad1)") (class "Default")
      (node (ref "R47") (pin "1") (pinfunction "1_1") (pintype "passive"))
      (node (ref "U8") (pin "8") (pinfunction "RG_8") (pintype "passive"))
    )
    (net (code "61") (name "Net-(U2B-IN-)") (class "Default")
      (node (ref "R2") (pin "1") (pinfunction "1_1") (pintype "passive"))
      (node (ref "R6") (pin "2") (pinfunction "2_2") (pintype "passive"))
      (node (ref "U2") (pin "6") (pinfunction "IN-_6") (pintype "input"))
    )
    (net (code "62") (name "Net-(U2B-OUT)") (class "Default")
      (node (ref "R2") (pin "2") (pinfunction "2_2") (pintype "passive"))
      (node (ref "R7") (pin "1") (pinfunction "1_1") (pintype "passive"))
      (node (ref "U2") (pin "7") (pinfunction "OUT_7") (pintype "output"))
    )
    (net (code "63") (name "Net-(U2C-IN+)") (class "Default")
      (node (ref "R8") (pin "1") (pinfunction "1_1") (pintype "passive"))
      (node (ref "U2") (pin "12") (pinfunction "IN+_12") (pintype "input"))
    )
    (net (code "64") (name "Net-(U2C-IN-)") (class "Default")
      (node (ref "R10") (pin "3") (pinfunction "3_3") (pintype "passive"))
      (node (ref "R5") (pin "2") (pinfunction "2_2") (pintype "passive"))
      (node (ref "U2") (pin "11") (pinfunction "IN-_11") (pintype "input"))
    )
    (net (code "65") (name "Net-(U2C-OUT)") (class "Default")
      (node (ref "R10") (pin "2") (pinfunction "2_2") (pintype "passive"))
      (node (ref "R14") (pin "2") (pinfunction "2_2") (pintype "passive"))
      (node (ref "R15") (pin "1") (pinfunction "1_1") (pintype "passive"))
      (node (ref "U2") (pin "10") (pinfunction "OUT_10") (pintype "output"))
    )
    (net (code "66") (name "Net-(U2D-IN+)") (class "Default")
      (node (ref "R11") (pin "1") (pinfunction "1_1") (pintype "passive"))
      (node (ref "R12") (pin "2") (pinfunction "2_2") (pintype "passive"))
      (node (ref "U2") (pin "14") (pinfunction "IN+_14") (pintype "input"))
    )
    (net (code "67") (name "Net-(U2D-IN-)") (class "Default")
      (node (ref "R15") (pin "2") (pinfunction "2_2") (pintype "passive"))
      (node (ref "R3") (pin "1") (pinfunction "1_1") (pintype "passive"))
      (node (ref "U2") (pin "15") (pinfunction "IN-_15") (pintype "input"))
    )
    (net (code "68") (name "Net-(U2D-OUT)") (class "Default")
      (node (ref "R3") (pin "2") (pinfunction "2_2") (pintype "passive"))
      (node (ref "R9") (pin "1") (pinfunction "1_1") (pintype "passive"))
      (node (ref "U2") (pin "16") (pinfunction "OUT_16") (pintype "output"))
    )
    (net (code "69") (name "Net-(U4B-IN-)") (class "Default")
      (node (ref "R13") (pin "1") (pinfunction "1_1") (pintype "passive"))
      (node (ref "R17") (pin "2") (pinfunction "2_2") (pintype "passive"))
      (node (ref "U4") (pin "6") (pinfunction "IN-_6") (pintype "input"))
    )
    (net (code "70") (name "Net-(U4B-OUT)") (class "Default")
      (node (ref "R13") (pin "2") (pinfunction "2_2") (pintype "passive"))
      (node (ref "R19") (pin "1") (pinfunction "1_1") (pintype "passive"))
      (node (ref "U4") (pin "7") (pinfunction "OUT_7") (pintype "output"))
    )
    (net (code "71") (name "Net-(U4C-IN+)") (class "Default")
      (node (ref "R22") (pin "1") (pinfunction "1_1") (pintype "passive"))
      (node (ref "U4") (pin "12") (pinfunction "IN+_12") (pintype "input"))
    )
    (net (code "72") (name "Net-(U4C-IN-)") (class "Default")
      (node (ref "R21") (pin "2") (pinfunction "2_2") (pintype "passive"))
      (node (ref "R24") (pin "3") (pinfunction "3_3") (pintype "passive"))
      (node (ref "U4") (pin "11") (pinfunction "IN-_11") (pintype "input"))
    )
    (net (code "73") (name "Net-(U4C-OUT)") (class "Default")
      (node (ref "R24") (pin "2") (pinfunction "2_2") (pintype "passive"))
      (node (ref "R28") (pin "2") (pinfunction "2_2") (pintype "passive"))
      (node (ref "R29") (pin "1") (pinfunction "1_1") (pintype "passive"))
      (node (ref "U4") (pin "10") (pinfunction "OUT_10") (pintype "output"))
    )
    (net (code "74") (name "Net-(U4D-IN+)") (class "Default")
      (node (ref "R26") (pin "1") (pinfunction "1_1") (pintype "passive"))
      (node (ref "R27") (pin "2") (pinfunction "2_2") (pintype "passive"))
      (node (ref "U4") (pin "14") (pinfunction "IN+_14") (pintype "input"))
    )
    (net (code "75") (name "Net-(U4D-IN-)") (class "Default")
      (node (ref "R20") (pin "1") (pinfunction "1_1") (pintype "passive"))
      (node (ref "R29") (pin "2") (pinfunction "2_2") (pintype "passive"))
      (node (ref "U4") (pin "15") (pinfunction "IN-_15") (pintype "input"))
    )
    (net (code "76") (name "Net-(U4D-OUT)") (class "Default")
      (node (ref "R20") (pin "2") (pinfunction "2_2") (pintype "passive"))
      (node (ref "R23") (pin "1") (pinfunction "1_1") (pintype "passive"))
      (node (ref "U4") (pin "16") (pinfunction "OUT_16") (pintype "output"))
    )
    (net (code "77") (name "Net-(U5B-IN-)") (class "Default")
      (node (ref "R25") (pin "1") (pinfunction "1_1") (pintype "passive"))
      (node (ref "R30") (pin "2") (pinfunction "2_2") (pintype "passive"))
      (node (ref "U5") (pin "6") (pinfunction "IN-_6") (pintype "input"))
    )
    (net (code "78") (name "Net-(U5B-OUT)") (class "Default")
      (node (ref "R25") (pin "2") (pinfunction "2_2") (pintype "passive"))
      (node (ref "R31") (pin "1") (pinfunction "1_1") (pintype "passive"))
      (node (ref "U5") (pin "7") (pinfunction "OUT_7") (pintype "output"))
    )
    (net (code "79") (name "Net-(U5C-IN+)") (class "Default")
      (node (ref "R37") (pin "1") (pinfunction "1_1") (pintype "passive"))
      (node (ref "U5") (pin "12") (pinfunction "IN+_12") (pintype "input"))
    )
    (net (code "80") (name "Net-(U5C-IN-)") (class "Default")
      (node (ref "R35") (pin "2") (pinfunction "2_2") (pintype "passive"))
      (node (ref "R39") (pin "3") (pinfunction "3_3") (pintype "passive"))
      (node (ref "U5") (pin "11") (pinfunction "IN-_11") (pintype "input"))
    )
    (net (code "81") (name "Net-(U5C-OUT)") (class "Default")
      (node (ref "R39") (pin "2") (pinfunction "2_2") (pintype "passive"))
      (node (ref "R44") (pin "2") (pinfunction "2_2") (pintype "passive"))
      (node (ref "R45") (pin "1") (pinfunction "1_1") (pintype "passive"))
      (node (ref "U5") (pin "10") (pinfunction "OUT_10") (pintype "output"))
    )
    (net (code "82") (name "Net-(U5D-IN+)") (class "Default")
      (node (ref "R42") (pin "1") (pinfunction "1_1") (pintype "passive"))
      (node (ref "R43") (pin "2") (pinfunction "2_2") (pintype "passive"))
      (node (ref "U5") (pin "14") (pinfunction "IN+_14") (pintype "input"))
    )
    (net (code "83") (name "Net-(U5D-IN-)") (class "Default")
      (node (ref "R34") (pin "1") (pinfunction "1_1") (pintype "passive"))
      (node (ref "R45") (pin "2") (pinfunction "2_2") (pintype "passive"))
      (node (ref "U5") (pin "15") (pinfunction "IN-_15") (pintype "input"))
    )
    (net (code "84") (name "Net-(U5D-OUT)") (class "Default")
      (node (ref "R34") (pin "2") (pinfunction "2_2") (pintype "passive"))
      (node (ref "R38") (pin "1") (pinfunction "1_1") (pintype "passive"))
      (node (ref "U5") (pin "16") (pinfunction "OUT_16") (pintype "output"))
    )
    (net (code "85") (name "Net-(U7B-IN-)") (class "Default")
      (node (ref "R36") (pin "1") (pinfunction "1_1") (pintype "passive"))
      (node (ref "R40") (pin "2") (pinfunction "2_2") (pintype "passive"))
      (node (ref "U7") (pin "6") (pinfunction "IN-_6") (pintype "input"))
    )
    (net (code "86") (name "Net-(U7B-OUT)") (class "Default")
      (node (ref "R36") (pin "2") (pinfunction "2_2") (pintype "passive"))
      (node (ref "R41") (pin "1") (pinfunction "1_1") (pintype "passive"))
      (node (ref "U7") (pin "7") (pinfunction "OUT_7") (pintype "output"))
    )
    (net (code "87") (name "Net-(U7C-IN+)") (class "Default")
      (node (ref "R50") (pin "1") (pinfunction "1_1") (pintype "passive"))
      (node (ref "U7") (pin "12") (pinfunction "IN+_12") (pintype "input"))
    )
    (net (code "88") (name "Net-(U7C-IN-)") (class "Default")
      (node (ref "R49") (pin "2") (pinfunction "2_2") (pintype "passive"))
      (node (ref "R52") (pin "3") (pinfunction "3_3") (pintype "passive"))
      (node (ref "U7") (pin "11") (pinfunction "IN-_11") (pintype "input"))
    )
    (net (code "89") (name "Net-(U7C-OUT)") (class "Default")
      (node (ref "R52") (pin "2") (pinfunction "2_2") (pintype "passive"))
      (node (ref "R55") (pin "2") (pinfunction "2_2") (pintype "passive"))
      (node (ref "R56") (pin "1") (pinfunction "1_1") (pintype "passive"))
      (node (ref "U7") (pin "10") (pinfunction "OUT_10") (pintype "output"))
    )
    (net (code "90") (name "Net-(U7D-IN+)") (class "Default")
      (node (ref "R53") (pin "1") (pinfunction "1_1") (pintype "passive"))
      (node (ref "R54") (pin "2") (pinfunction "2_2") (pintype "passive"))
      (node (ref "U7") (pin "14") (pinfunction "IN+_14") (pintype "input"))
    )
    (net (code "91") (name "Net-(U7D-IN-)") (class "Default")
      (node (ref "R48") (pin "1") (pinfunction "1_1") (pintype "passive"))
      (node (ref "R56") (pin "2") (pinfunction "2_2") (pintype "passive"))
      (node (ref "U7") (pin "15") (pinfunction "IN-_15") (pintype "input"))
    )
    (net (code "92") (name "Net-(U7D-OUT)") (class "Default")
      (node (ref "R48") (pin "2") (pinfunction "2_2") (pintype "passive"))
      (node (ref "R51") (pin "1") (pinfunction "1_1") (pintype "passive"))
      (node (ref "U7") (pin "16") (pinfunction "OUT_16") (pintype "output"))
    )
    (net (code "93") (name "Net-(U9-+_IN_A)") (class "Default")
      (node (ref "C15") (pin "1") (pinfunction "1_1") (pintype "passive"))
      (node (ref "R61") (pin "1") (pinfunction "1_1") (pintype "passive"))
      (node (ref "U9") (pin "3") (pinfunction "+_IN_A_3") (pintype "input"))
    )
    (net (code "94") (name "Net-(U9-+_IN_B)") (class "Default")
      (node (ref "C22") (pin "2") (pinfunction "2_2") (pintype "passive"))
      (node (ref "R66") (pin "1") (pinfunction "1_1") (pintype "passive"))
      (node (ref "U9") (pin "5") (pinfunction "+_IN_B_5") (pintype "input"))
    )
    (net (code "95") (name "Net-(U10-+_IN_A)") (class "Default")
      (node (ref "C19") (pin "1") (pinfunction "1_1") (pintype "passive"))
      (node (ref "R63") (pin "1") (pinfunction "1_1") (pintype "passive"))
      (node (ref "U10") (pin "3") (pinfunction "+_IN_A_3") (pintype "input"))
    )
    (net (code "96") (name "Net-(U10-+_IN_B)") (class "Default")
      (node (ref "C24") (pin "2") (pinfunction "2_2") (pintype "passive"))
      (node (ref "R70") (pin "1") (pinfunction "1_1") (pintype "passive"))
      (node (ref "U10") (pin "5") (pinfunction "+_IN_B_5") (pintype "input"))
    )
    (net (code "97") (name "unconnected-(P4-Pad4)") (class "Default")
      (node (ref "P4") (pin "4") (pinfunction "4_4") (pintype "passive+no_connect"))
    )
    (net (code "98") (name "unconnected-(R10-Pad1)") (class "Default")
      (node (ref "R10") (pin "1") (pinfunction "1_1") (pintype "passive+no_connect"))
    )
    (net (code "99") (name "unconnected-(R24-Pad1)") (class "Default")
      (node (ref "R24") (pin "1") (pinfunction "1_1") (pintype "passive+no_connect"))
    )
    (net (code "100") (name "unconnected-(R39-Pad1)") (class "Default")
      (node (ref "R39") (pin "1") (pinfunction "1_1") (pintype "passive+no_connect"))
    )
    (net (code "101") (name "unconnected-(R52-Pad1)") (class "Default")
      (node (ref "R52") (pin "1") (pinfunction "1_1") (pintype "passive+no_connect"))
    )
    (net (code "102") (name "unconnected-(U11-NC-Pad1)") (class "Default")
      (node (ref "U11") (pin "1") (pinfunction "NC_1") (pintype "passive+no_connect"))
    )
    (net (code "103") (name "unconnected-(U11-NC-Pad3)") (class "Default")
      (node (ref "U11") (pin "3") (pinfunction "NC_3") (pintype "passive+no_connect"))
    )
  )
)
